# Main.net
KiCad netlist of a schematic drawn in Altium Designer
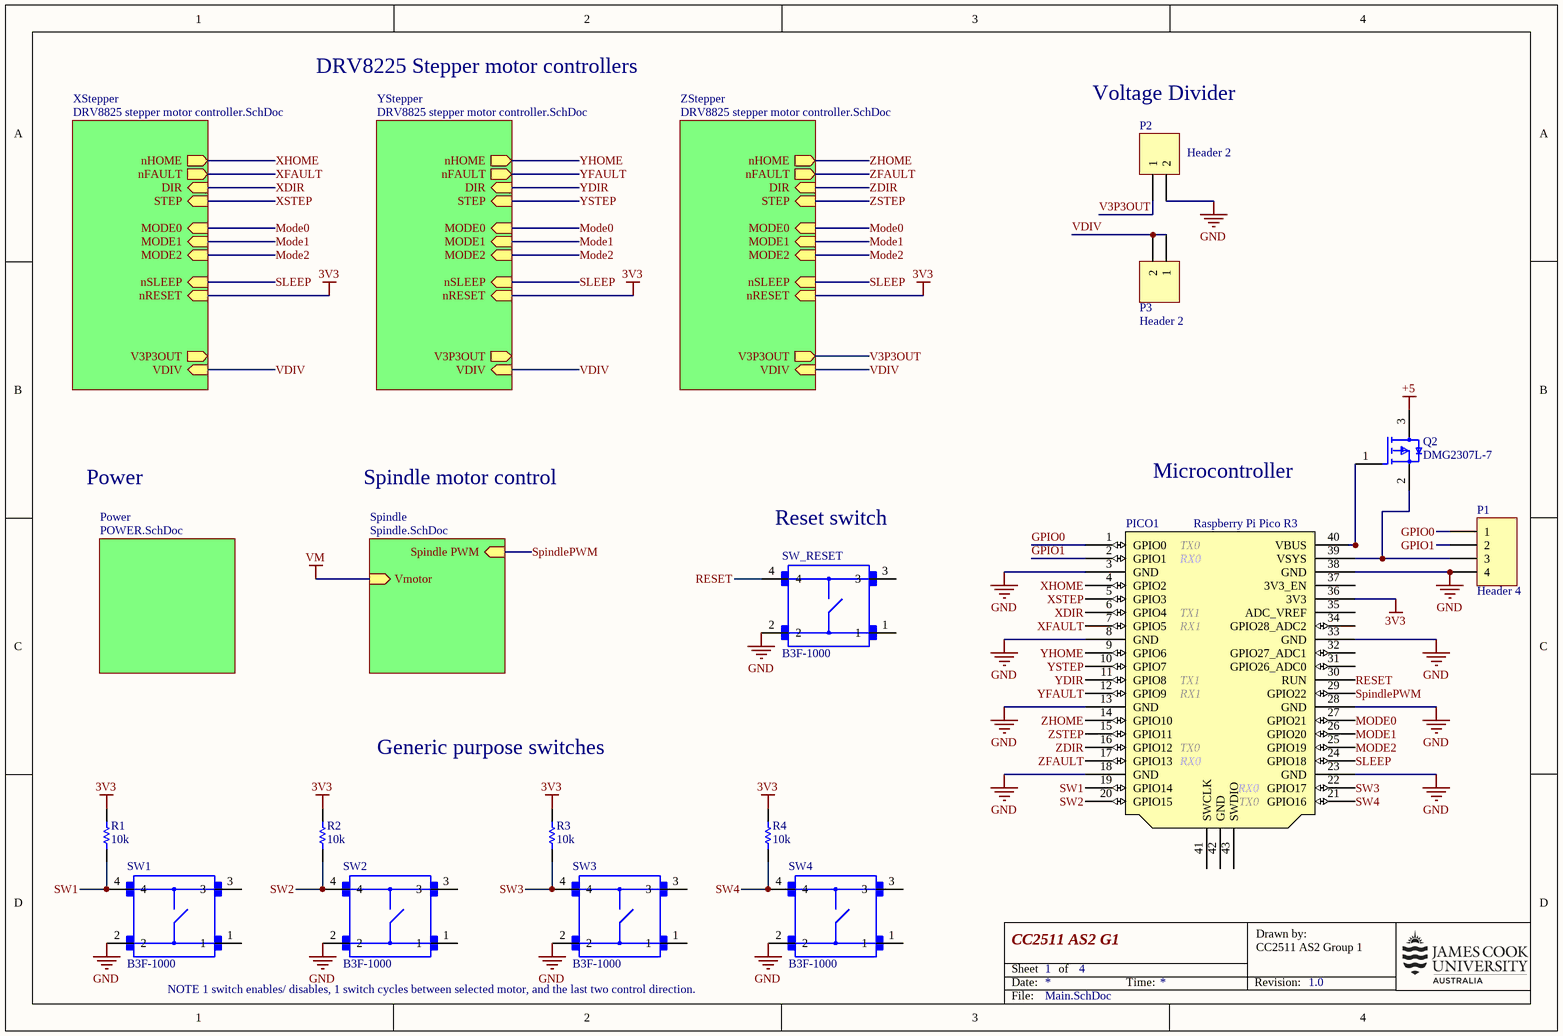
[diagram p0: Main.SchDoc]

(export (version "E")
  (design (tool "Eeschema 10.0.6"))
  (components
    (comp (ref "P1")
      (value "Header 4")
      (footprint "HDR1X4")
      (description "Header, 4-Pin")
      (fields (field (name "PUBLISHER") "Altium Limited"))
      (libsource (lib "Miscellaneous Connectors") (part "Header 4"))
    )
    (comp (ref "P2")
      (value "Header 2")
      (footprint "HDR1X2")
      (description "Header, 2-Pin")
      (fields (field (name "PUBLISHER") "Altium Limited"))
      (libsource (lib "Miscellaneous Connectors") (part "Header 2"))
    )
    (comp (ref "P3")
      (value "Header 2")
      (footprint "HDR1X2")
      (description "Header, 2-Pin")
      (fields (field (name "PUBLISHER") "Altium Limited"))
      (libsource (lib "") (part "Header 2_1"))
    )
    (comp (ref "PICO1")
      (value "Raspberry Pi Pico R3")
      (footprint "RASPI_PICO_83")
      (libsource (lib "JCULibrary_AS2_v2") (part "Rapberry Pi Pico-R3"))
    )
    (comp (ref "Q2")
      (value "DMG2307L-7")
      (footprint "FP-SOT23-MFG")
      (description "MOSFET P-CH 30V 2.5A SOT-23")
      (libsource (lib "Altium Content Vault") (part "93d33217dd9b7373daa85f78e0218cc"))
    )
    (comp (ref "R1")
      (value "10k")
      (footprint "RESC2013X60X35ML10T20")
      (description "Chip Resistor, 10 KOhm, +/- 5%, 0.125 W, -55 to 155 degC, 0805 (2012 Metric), RoHS, Tape and Reel")
      (fields (field (name "MANUFACTURER") "Yageo"))
      (libsource (lib "Altium Content Vault") (part "RES-2"))
    )
    (comp (ref "R2")
      (value "10k")
      (footprint "RESC2013X60X35ML10T20")
      (description "Chip Resistor, 10 KOhm, +/- 5%, 0.125 W, -55 to 155 degC, 0805 (2012 Metric), RoHS, Tape and Reel")
      (fields (field (name "MANUFACTURER") "Yageo"))
      (libsource (lib "Altium Content Vault") (part "RES-2"))
    )
    (comp (ref "R3")
      (value "10k")
      (footprint "RESC2013X60X35ML10T20")
      (description "Chip Resistor, 10 KOhm, +/- 5%, 0.125 W, -55 to 155 degC, 0805 (2012 Metric), RoHS, Tape and Reel")
      (fields (field (name "MANUFACTURER") "Yageo"))
      (libsource (lib "Altium Content Vault") (part "RES-2"))
    )
    (comp (ref "R4")
      (value "10k")
      (footprint "RESC2013X60X35ML10T20")
      (description "Chip Resistor, 10 KOhm, +/- 5%, 0.125 W, -55 to 155 degC, 0805 (2012 Metric), RoHS, Tape and Reel")
      (fields (field (name "MANUFACTURER") "Yageo"))
      (libsource (lib "Altium Content Vault") (part "RES-2"))
    )
    (comp (ref "SW1")
      (value "B3F-1000")
      (footprint "SW_B3F-1000")
      (description "Switch Tactile N.O. SPST Flat Round Button PC Pins 0.05A 24VDC 1000000Cycles 0.98N Thru-Hole Bag")
      (fields (field (name "MF") "Omron"))
      (libsource (lib "JCULibrary") (part "B3F-1000"))
    )
    (comp (ref "SW2")
      (value "B3F-1000")
      (footprint "SW_B3F-1000")
      (description "Switch Tactile N.O. SPST Flat Round Button PC Pins 0.05A 24VDC 1000000Cycles 0.98N Thru-Hole Bag")
      (fields (field (name "MF") "Omron"))
      (libsource (lib "JCULibrary") (part "B3F-1000"))
    )
    (comp (ref "SW3")
      (value "B3F-1000")
      (footprint "SW_B3F-1000")
      (description "Switch Tactile N.O. SPST Flat Round Button PC Pins 0.05A 24VDC 1000000Cycles 0.98N Thru-Hole Bag")
      (fields (field (name "MF") "Omron"))
      (libsource (lib "JCULibrary") (part "B3F-1000"))
    )
    (comp (ref "SW4")
      (value "B3F-1000")
      (footprint "SW_B3F-1000")
      (description "Switch Tactile N.O. SPST Flat Round Button PC Pins 0.05A 24VDC 1000000Cycles 0.98N Thru-Hole Bag")
      (fields (field (name "MF") "Omron"))
      (libsource (lib "JCULibrary") (part "B3F-1000"))
    )
    (comp (ref "SW_RESET")
      (value "B3F-1000")
      (footprint "SW_B3F-1000")
      (description "Switch Tactile N.O. SPST Flat Round Button PC Pins 0.05A 24VDC 1000000Cycles 0.98N Thru-Hole Bag")
      (fields (field (name "MF") "Omron"))
      (libsource (lib "JCULibrary") (part "B3F-1000"))
    )
  )
  (nets
    (net (code "1") (name "+5") (class "Default")
      (node (ref "Q2") (pin "3") (pinfunction "D_3") (pintype "passive"))
    )
    (net (code "2") (name "/GPIO0") (class "Default")
      (node (ref "P1") (pin "1") (pinfunction "1_1") (pintype "passive"))
      (node (ref "PICO1") (pin "1") (pinfunction "GPIO0_1") (pintype "bidirectional"))
    )
    (net (code "3") (name "/GPIO1") (class "Default")
      (node (ref "P1") (pin "2") (pinfunction "2_2") (pintype "passive"))
      (node (ref "PICO1") (pin "2") (pinfunction "GPIO1_2") (pintype "bidirectional"))
    )
    (net (code "4") (name "/MODE0") (class "Default")
      (node (ref "PICO1") (pin "27") (pinfunction "GPIO21_27") (pintype "bidirectional"))
    )
    (net (code "5") (name "/MODE1") (class "Default")
      (node (ref "PICO1") (pin "26") (pinfunction "GPIO20_26") (pintype "bidirectional"))
    )
    (net (code "6") (name "/MODE2") (class "Default")
      (node (ref "PICO1") (pin "25") (pinfunction "GPIO19_25") (pintype "bidirectional"))
    )
    (net (code "10") (name "/RESET") (class "Default")
      (node (ref "PICO1") (pin "30") (pinfunction "RUN_30") (pintype "passive"))
      (node (ref "SW_RESET") (pin "4") (pinfunction "4_4") (pintype "passive"))
    )
    (net (code "11") (name "/SLEEP") (class "Default")
      (node (ref "PICO1") (pin "24") (pinfunction "GPIO18_24") (pintype "bidirectional"))
    )
    (net (code "12") (name "/SW1") (class "Default")
      (node (ref "PICO1") (pin "19") (pinfunction "GPIO14_19") (pintype "bidirectional"))
      (node (ref "R1") (pin "2") (pinfunction "2_2") (pintype "passive"))
      (node (ref "SW1") (pin "4") (pinfunction "4_4") (pintype "passive"))
    )
    (net (code "13") (name "/SW2") (class "Default")
      (node (ref "PICO1") (pin "20") (pinfunction "GPIO15_20") (pintype "bidirectional"))
      (node (ref "R2") (pin "2") (pinfunction "2_2") (pintype "passive"))
      (node (ref "SW2") (pin "4") (pinfunction "4_4") (pintype "passive"))
    )
    (net (code "14") (name "/SW3") (class "Default")
      (node (ref "PICO1") (pin "22") (pinfunction "GPIO17_22") (pintype "bidirectional"))
      (node (ref "R3") (pin "2") (pinfunction "2_2") (pintype "passive"))
      (node (ref "SW3") (pin "4") (pinfunction "4_4") (pintype "passive"))
    )
    (net (code "15") (name "/SW4") (class "Default")
      (node (ref "PICO1") (pin "21") (pinfunction "GPIO16_21") (pintype "bidirectional"))
      (node (ref "R4") (pin "2") (pinfunction "2_2") (pintype "passive"))
      (node (ref "SW4") (pin "4") (pinfunction "4_4") (pintype "passive"))
    )
    (net (code "16") (name "/SpindlePWM") (class "Default")
      (node (ref "PICO1") (pin "29") (pinfunction "GPIO22_29") (pintype "bidirectional"))
    )
    (net (code "17") (name "/V3P3OUT") (class "Default")
      (node (ref "P2") (pin "1") (pinfunction "1_1") (pintype "passive"))
    )
    (net (code "20") (name "/VDIV") (class "Default")
      (node (ref "P3") (pin "1") (pinfunction "1_1") (pintype "passive"))
      (node (ref "P3") (pin "2") (pinfunction "2_2") (pintype "passive"))
    )
    (net (code "21") (name "/XDIR") (class "Default")
      (node (ref "PICO1") (pin "6") (pinfunction "GPIO4_6") (pintype "bidirectional"))
    )
    (net (code "22") (name "/XFAULT") (class "Default")
      (node (ref "PICO1") (pin "7") (pinfunction "GPIO5_7") (pintype "bidirectional"))
    )
    (net (code "23") (name "/XHOME") (class "Default")
      (node (ref "PICO1") (pin "4") (pinfunction "GPIO2_4") (pintype "bidirectional"))
    )
    (net (code "24") (name "/XSTEP") (class "Default")
      (node (ref "PICO1") (pin "5") (pinfunction "GPIO3_5") (pintype "bidirectional"))
    )
    (net (code "25") (name "/YDIR") (class "Default")
      (node (ref "PICO1") (pin "11") (pinfunction "GPIO8_11") (pintype "bidirectional"))
    )
    (net (code "26") (name "/YFAULT") (class "Default")
      (node (ref "PICO1") (pin "12") (pinfunction "GPIO9_12") (pintype "bidirectional"))
    )
    (net (code "27") (name "/YHOME") (class "Default")
      (node (ref "PICO1") (pin "9") (pinfunction "GPIO6_9") (pintype "bidirectional"))
    )
    (net (code "28") (name "/YSTEP") (class "Default")
      (node (ref "PICO1") (pin "10") (pinfunction "GPIO7_10") (pintype "bidirectional"))
    )
    (net (code "29") (name "/ZDIR") (class "Default")
      (node (ref "PICO1") (pin "16") (pinfunction "GPIO12_16") (pintype "bidirectional"))
    )
    (net (code "30") (name "/ZFAULT") (class "Default")
      (node (ref "PICO1") (pin "17") (pinfunction "GPIO13_17") (pintype "bidirectional"))
    )
    (net (code "31") (name "/ZHOME") (class "Default")
      (node (ref "PICO1") (pin "14") (pinfunction "GPIO10_14") (pintype "bidirectional"))
    )
    (net (code "32") (name "/ZSTEP") (class "Default")
      (node (ref "PICO1") (pin "15") (pinfunction "GPIO11_15") (pintype "bidirectional"))
    )
    (net (code "33") (name "3V3") (class "Default")
      (node (ref "PICO1") (pin "36") (pinfunction "3V3_36") (pintype "power_in"))
      (node (ref "R1") (pin "1") (pinfunction "1_1") (pintype "passive"))
      (node (ref "R2") (pin "1") (pinfunction "1_1") (pintype "passive"))
      (node (ref "R3") (pin "1") (pinfunction "1_1") (pintype "passive"))
      (node (ref "R4") (pin "1") (pinfunction "1_1") (pintype "passive"))
    )
    (net (code "34") (name "GND") (class "Default")
      (node (ref "P1") (pin "4") (pinfunction "4_4") (pintype "passive"))
      (node (ref "P2") (pin "2") (pinfunction "2_2") (pintype "passive"))
      (node (ref "PICO1") (pin "13") (pinfunction "GND_13") (pintype "power_in"))
      (node (ref "PICO1") (pin "18") (pinfunction "GND_18") (pintype "power_in"))
      (node (ref "PICO1") (pin "23") (pinfunction "GND_23") (pintype "power_in"))
      (node (ref "PICO1") (pin "28") (pinfunction "GND_28") (pintype "power_in"))
      (node (ref "PICO1") (pin "3") (pinfunction "GND_3") (pintype "power_in"))
      (node (ref "PICO1") (pin "33") (pinfunction "GND_33") (pintype "power_in"))
      (node (ref "PICO1") (pin "38") (pinfunction "GND_38") (pintype "power_in"))
      (node (ref "PICO1") (pin "8") (pinfunction "GND_8") (pintype "power_in"))
      (node (ref "SW1") (pin "2") (pinfunction "2_2") (pintype "passive"))
      (node (ref "SW2") (pin "2") (pinfunction "2_2") (pintype "passive"))
      (node (ref "SW3") (pin "2") (pinfunction "2_2") (pintype "passive"))
      (node (ref "SW4") (pin "2") (pinfunction "2_2") (pintype "passive"))
      (node (ref "SW_RESET") (pin "2") (pinfunction "2_2") (pintype "passive"))
    )
    (net (code "35") (name "Net-(PICO1-VBUS)") (class "Default")
      (node (ref "PICO1") (pin "40") (pinfunction "VBUS_40") (pintype "power_in"))
      (node (ref "Q2") (pin "1") (pinfunction "G_1") (pintype "passive"))
    )
    (net (code "36") (name "Net-(PICO1-VSYS)") (class "Default")
      (node (ref "P1") (pin "3") (pinfunction "3_3") (pintype "passive"))
      (node (ref "PICO1") (pin "39") (pinfunction "VSYS_39") (pintype "power_in"))
      (node (ref "Q2") (pin "2") (pinfunction "S_2") (pintype "passive"))
    )
    (net (code "38") (name "unconnected-(PICO1-3V3_EN-Pad37)") (class "Default")
      (node (ref "PICO1") (pin "37") (pinfunction "3V3_EN_37") (pintype "power_in"))
    )
    (net (code "39") (name "unconnected-(PICO1-ADC_VREF-Pad35)") (class "Default")
      (node (ref "PICO1") (pin "35") (pinfunction "ADC_VREF_35") (pintype "passive"))
    )
    (net (code "40") (name "unconnected-(PICO1-GND-Pad42)") (class "Default")
      (node (ref "PICO1") (pin "42") (pinfunction "GND_42") (pintype "power_in"))
    )
    (net (code "41") (name "unconnected-(PICO1-GPIO26_ADC0-Pad31)") (class "Default")
      (node (ref "PICO1") (pin "31") (pinfunction "GPIO26_ADC0_31") (pintype "bidirectional"))
    )
    (net (code "42") (name "unconnected-(PICO1-GPIO27_ADC1-Pad32)") (class "Default")
      (node (ref "PICO1") (pin "32") (pinfunction "GPIO27_ADC1_32") (pintype "bidirectional"))
    )
    (net (code "43") (name "unconnected-(PICO1-GPIO28_ADC2-Pad34)") (class "Default")
      (node (ref "PICO1") (pin "34") (pinfunction "GPIO28_ADC2_34") (pintype "bidirectional"))
    )
    (net (code "44") (name "unconnected-(PICO1-SWCLK-Pad41)") (class "Default")
      (node (ref "PICO1") (pin "41") (pinfunction "SWCLK_41") (pintype "passive"))
    )
    (net (code "45") (name "unconnected-(PICO1-SWDIO-Pad43)") (class "Default")
      (node (ref "PICO1") (pin "43") (pinfunction "SWDIO_43") (pintype "passive"))
    )
    (net (code "46") (name "unconnected-(SW1-Pad1)") (class "Default")
      (node (ref "SW1") (pin "1") (pinfunction "1_1") (pintype "passive"))
    )
    (net (code "47") (name "unconnected-(SW1-Pad3)") (class "Default")
      (node (ref "SW1") (pin "3") (pinfunction "3_3") (pintype "passive"))
    )
    (net (code "48") (name "unconnected-(SW2-Pad1)") (class "Default")
      (node (ref "SW2") (pin "1") (pinfunction "1_1") (pintype "passive"))
    )
    (net (code "49") (name "unconnected-(SW2-Pad3)") (class "Default")
      (node (ref "SW2") (pin "3") (pinfunction "3_3") (pintype "passive"))
    )
    (net (code "50") (name "unconnected-(SW3-Pad1)") (class "Default")
      (node (ref "SW3") (pin "1") (pinfunction "1_1") (pintype "passive"))
    )
    (net (code "51") (name "unconnected-(SW3-Pad3)") (class "Default")
      (node (ref "SW3") (pin "3") (pinfunction "3_3") (pintype "passive"))
    )
    (net (code "52") (name "unconnected-(SW4-Pad1)") (class "Default")
      (node (ref "SW4") (pin "1") (pinfunction "1_1") (pintype "passive"))
    )
    (net (code "53") (name "unconnected-(SW4-Pad3)") (class "Default")
      (node (ref "SW4") (pin "3") (pinfunction "3_3") (pintype "passive"))
    )
    (net (code "54") (name "unconnected-(SW_RESET-Pad1)") (class "Default")
      (node (ref "SW_RESET") (pin "1") (pinfunction "1_1") (pintype "passive"))
    )
    (net (code "55") (name "unconnected-(SW_RESET-Pad3)") (class "Default")
      (node (ref "SW_RESET") (pin "3") (pinfunction "3_3") (pintype "passive"))
    )
  )
)
